# Hall_Effect_IC.net
KiCad netlist of a schematic drawn in Altium Designer
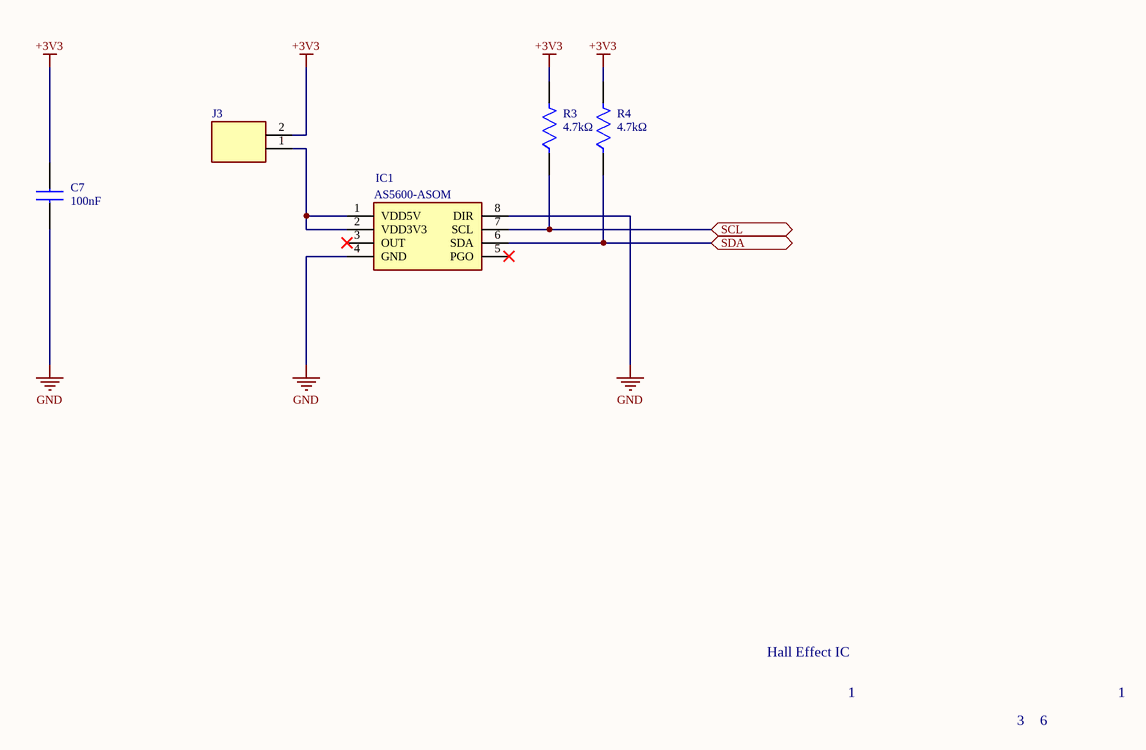
[diagram p0: Hall Effect IC.SchDoc]

(export (version "E")
  (design (tool "Eeschema 10.0.6"))
  (components
    (comp (ref "C7")
      (value "100nF")
      (footprint "SamacSys:CAPC2013X137N")
      (description "Capacitor")
      (fields
        (field (name "MANUFACTURER_PART_NUMBER") "0805B104K500NT")
        (field (name "MOUSER PART NUMBER") "767-0805B104K500NT")
      )
      (libsource (lib "*") (part "0805B104K500NT"))
    )
    (comp (ref "IC1")
      (value "AS5600-ASOM")
      (footprint "SamacSys:SOIC127P600X175-8N")
      (description "Integrated Circuit")
      (fields (field (name "MOUSER PART NUMBER") "985-AS5600-ASOM"))
      (libsource (lib "*") (part "AS5600-ASOM"))
    )
    (comp (ref "J3")
      (value "87527-2")
      (footprint "SamacSys:HDRV2W66P0X254_1X2_467X244X1044P")
      (description "Power isolation jumper")
      (fields (field (name "MOUSER PART NUMBER") "571-875272"))
      (libsource (lib "*") (part "87527-2"))
    )
    (comp (ref "R3")
      (value "4.7kΩ")
      (footprint "FP-RT0805-MFG")
      (description "RES SMD 4.7K OHM 0.5% 1/8W 0805")
      (fields
        (field (name "OCTOPART") "https://octopart.com/rt0805dre074k7l-yageo-1242027")
        (field (name "TOLERANCE") "0.01")
      )
      (libsource (lib "Altium Content Vault") (part "1029c3af85768c4190bb7ad29bc67b5"))
    )
    (comp (ref "R4")
      (value "4.7kΩ")
      (footprint "FP-RT0805-MFG")
      (description "RES SMD 4.7K OHM 0.5% 1/8W 0805")
      (fields
        (field (name "OCTOPART") "https://octopart.com/rt0805dre074k7l-yageo-1242027")
        (field (name "TOLERANCE") "0.01")
      )
      (libsource (lib "Altium Content Vault") (part "1029c3af85768c4190bb7ad29bc67b5"))
    )
  )
  (nets
    (net (code "1") (name "+3V3") (class "Default")
      (node (ref "C7") (pin "1") (pinfunction "1_1") (pintype "passive"))
      (node (ref "J3") (pin "2") (pinfunction "2_2") (pintype "passive"))
      (node (ref "R3") (pin "2") (pinfunction "2_2") (pintype "passive"))
      (node (ref "R4") (pin "2") (pinfunction "2_2") (pintype "passive"))
    )
    (net (code "2") (name "/SCL") (class "Default")
      (node (ref "IC1") (pin "7") (pinfunction "SCL_7") (pintype "passive"))
      (node (ref "R3") (pin "1") (pinfunction "1_1") (pintype "passive"))
    )
    (net (code "3") (name "/SDA") (class "Default")
      (node (ref "IC1") (pin "6") (pinfunction "SDA_6") (pintype "passive"))
      (node (ref "R4") (pin "1") (pinfunction "1_1") (pintype "passive"))
    )
    (net (code "4") (name "GND") (class "Default")
      (node (ref "C7") (pin "2") (pinfunction "2_2") (pintype "passive"))
      (node (ref "IC1") (pin "4") (pinfunction "GND_4") (pintype "passive"))
      (node (ref "IC1") (pin "8") (pinfunction "DIR_8") (pintype "passive"))
    )
    (net (code "5") (name "Net-(IC1-VDD3V3)") (class "Default")
      (node (ref "IC1") (pin "1") (pinfunction "VDD5V_1") (pintype "passive"))
      (node (ref "IC1") (pin "2") (pinfunction "VDD3V3_2") (pintype "passive"))
      (node (ref "J3") (pin "1") (pinfunction "1_1") (pintype "passive"))
    )
    (net (code "6") (name "unconnected-(IC1-OUT-Pad3)") (class "Default")
      (node (ref "IC1") (pin "3") (pinfunction "OUT_3") (pintype "passive+no_connect"))
    )
    (net (code "7") (name "unconnected-(IC1-PGO-Pad5)") (class "Default")
      (node (ref "IC1") (pin "5") (pinfunction "PGO_5") (pintype "passive+no_connect"))
    )
  )
)
